# Mainboard.net
KiCad netlist of a schematic drawn in EAGLE
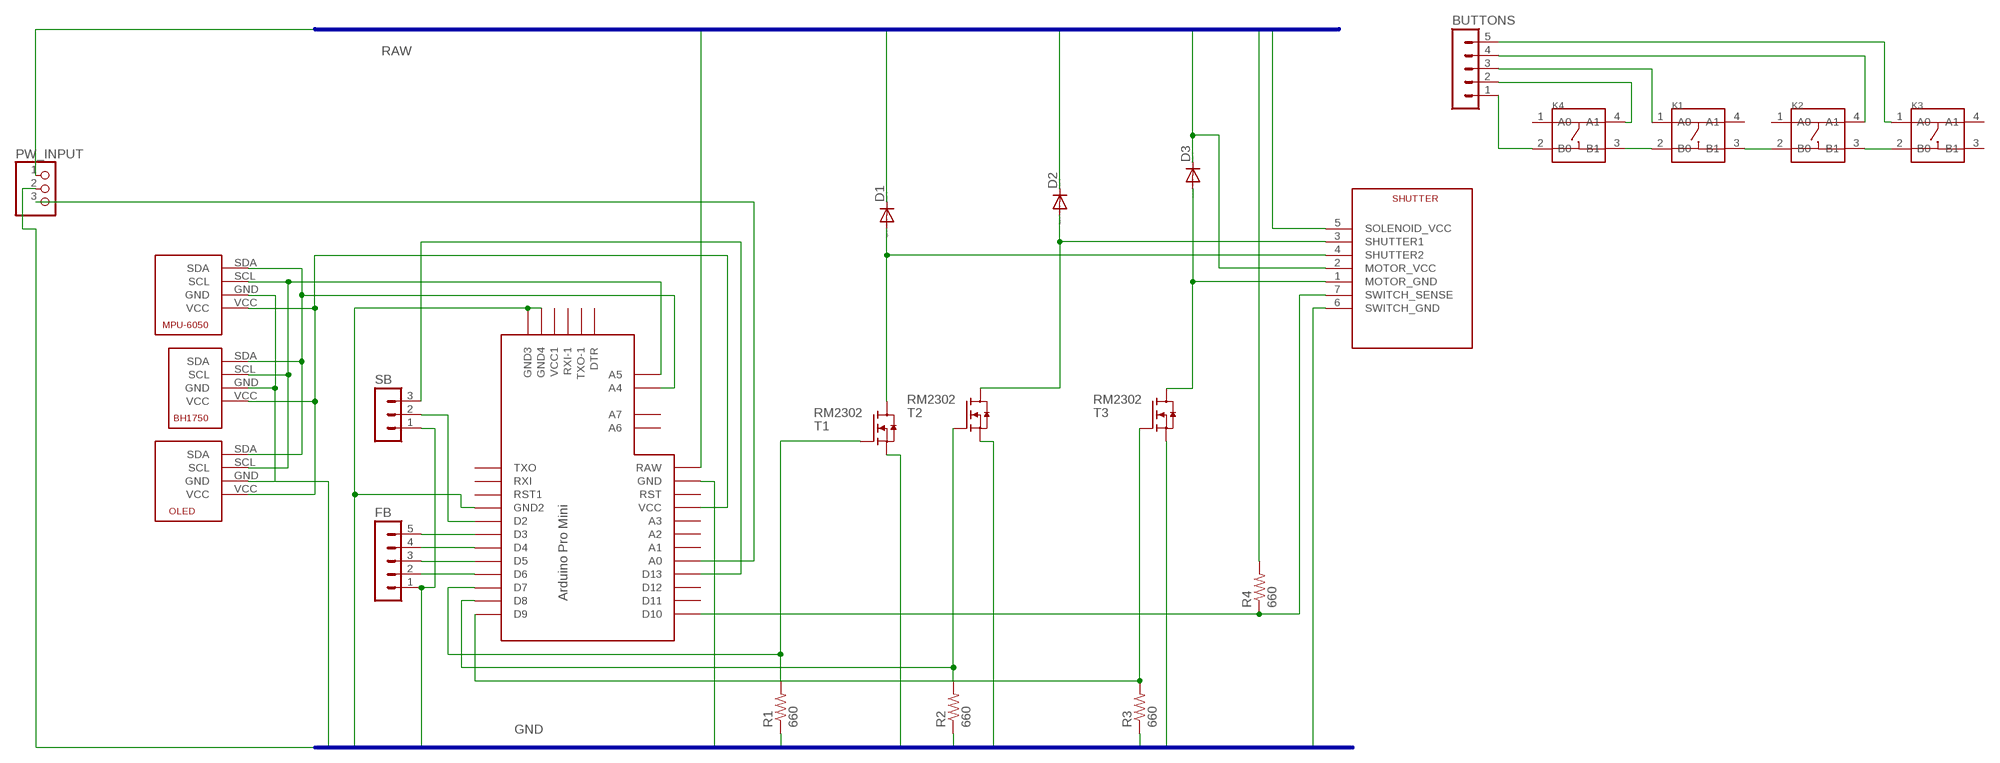
[diagram p0: schematic, sheet 1]

(export (version "E")
  (design (tool "Eeschema 10.0.6"))
  (components
    (comp (ref "BH1750")
      (value "BH1750")
      (footprint "eagle-import:MA04-1")
      (libsource (lib "eagle-import") (part "BH1750"))
    )
    (comp (ref "BUTTONS")
      (value "MA05-1")
      (footprint "eagle-import:MA05-1")
      (libsource (lib "eagle-import") (part "MA05-1"))
    )
    (comp (ref "D1")
      (value "DIODE-D-5")
      (footprint "eagle-import:D-5")
      (libsource (lib "eagle-import") (part "DIODE-D-5"))
    )
    (comp (ref "D2")
      (value "DIODE-D-5")
      (footprint "eagle-import:D-5")
      (libsource (lib "eagle-import") (part "DIODE-D-5"))
    )
    (comp (ref "D3")
      (value "DIODE-D-5")
      (footprint "eagle-import:D-5")
      (libsource (lib "eagle-import") (part "DIODE-D-5"))
    )
    (comp (ref "FB")
      (value "MA05-1")
      (footprint "eagle-import:MA05-1")
      (libsource (lib "eagle-import") (part "MA05-1"))
    )
    (comp (ref "K1")
      (value "SMD-SWITCH-TACTILE-SPST-NO(4P-D6.0MM)")
      (footprint "eagle-import:SW4-SMD-6.0X6.0X5.0MM")
      (fields (field (name "MPN") "DTSM-62K-S-V-T/R(SN431)"))
      (libsource (lib "eagle-import") (part "SMD-SWITCH-TACTILE-SPST-NO(4P-D6.0MM)"))
    )
    (comp (ref "K2")
      (value "SMD-SWITCH-TACTILE-SPST-NO(4P-D6.0MM)")
      (footprint "eagle-import:SW4-SMD-6.0X6.0X5.0MM")
      (fields (field (name "MPN") "DTSM-62K-S-V-T/R(SN431)"))
      (libsource (lib "eagle-import") (part "SMD-SWITCH-TACTILE-SPST-NO(4P-D6.0MM)"))
    )
    (comp (ref "K3")
      (value "SMD-SWITCH-TACTILE-SPST-NO(4P-D6.0MM)")
      (footprint "eagle-import:SW4-SMD-6.0X6.0X5.0MM")
      (fields (field (name "MPN") "DTSM-62K-S-V-T/R(SN431)"))
      (libsource (lib "eagle-import") (part "SMD-SWITCH-TACTILE-SPST-NO(4P-D6.0MM)"))
    )
    (comp (ref "K4")
      (value "SMD-SWITCH-TACTILE-SPST-NO(4P-D6.0MM)")
      (footprint "eagle-import:SW4-SMD-6.0X6.0X5.0MM")
      (fields (field (name "MPN") "DTSM-62K-S-V-T/R(SN431)"))
      (libsource (lib "eagle-import") (part "SMD-SWITCH-TACTILE-SPST-NO(4P-D6.0MM)"))
    )
    (comp (ref "MPU6050")
      (value "MPU-6050")
      (footprint "eagle-import:MA04-1")
      (libsource (lib "eagle-import") (part "MPU-6050"))
    )
    (comp (ref "OLED")
      (value "OLED")
      (footprint "eagle-import:MA04-1")
      (libsource (lib "eagle-import") (part "OLED"))
    )
    (comp (ref "PW_INPUT")
      (value "PINHD-1X3")
      (footprint "eagle-import:1X03")
      (libsource (lib "eagle-import") (part "PINHD-1X3"))
    )
    (comp (ref "R1")
      (value "660")
      (footprint "eagle-import:0204V")
      (libsource (lib "eagle-import") (part "R-US_0204/2V"))
    )
    (comp (ref "R2")
      (value "660")
      (footprint "eagle-import:0204V")
      (libsource (lib "eagle-import") (part "R-US_0204/2V"))
    )
    (comp (ref "R3")
      (value "660")
      (footprint "eagle-import:0204V")
      (libsource (lib "eagle-import") (part "R-US_0204/2V"))
    )
    (comp (ref "R4")
      (value "660")
      (footprint "eagle-import:0204V")
      (libsource (lib "eagle-import") (part "R-US_0204/2V"))
    )
    (comp (ref "SB")
      (value "MA03-1")
      (footprint "eagle-import:MA03-1")
      (libsource (lib "eagle-import") (part "MA03-1"))
    )
    (comp (ref "T1")
      (value "RM2302")
      (footprint "eagle-import:SOT23")
      (libsource (lib "eagle-import") (part "RM2302"))
    )
    (comp (ref "T2")
      (value "RM2302")
      (footprint "eagle-import:SOT23")
      (libsource (lib "eagle-import") (part "RM2302"))
    )
    (comp (ref "T3")
      (value "RM2302")
      (footprint "eagle-import:SOT23")
      (libsource (lib "eagle-import") (part "RM2302"))
    )
    (comp (ref "U$1")
      (value "SHUTTER")
      (footprint "eagle-import:MA07-1")
      (libsource (lib "eagle-import") (part "SHUTTER"))
    )
    (comp (ref "U$7")
      (value "PRO-MINI-2")
      (footprint "eagle-import:PRO-MINI-2")
      (libsource (lib "eagle-import") (part "PRO-MINI-2"))
    )
  )
  (nets
    (net (code "2") (name "/BTG") (class "Default")
      (node (ref "BUTTONS") (pin "1") (pinfunction "1_1") (pintype "passive"))
      (node (ref "K1") (pin "2") (pinfunction "B0_2") (pintype "bidirectional"))
      (node (ref "K1") (pin "3") (pinfunction "B1_3") (pintype "bidirectional"))
      (node (ref "K2") (pin "2") (pinfunction "B0_2") (pintype "bidirectional"))
      (node (ref "K2") (pin "3") (pinfunction "B1_3") (pintype "bidirectional"))
      (node (ref "K3") (pin "2") (pinfunction "B0_2") (pintype "bidirectional"))
      (node (ref "K4") (pin "2") (pinfunction "B0_2") (pintype "bidirectional"))
      (node (ref "K4") (pin "3") (pinfunction "B1_3") (pintype "bidirectional"))
    )
    (net (code "3") (name "/GND") (class "Default")
      (node (ref "BH1750") (pin "GND") (pinfunction "GND_GND") (pintype "power_in"))
      (node (ref "FB") (pin "1") (pinfunction "1_1") (pintype "passive"))
      (node (ref "MPU6050") (pin "GND") (pinfunction "GND_GND") (pintype "power_in"))
      (node (ref "OLED") (pin "GND") (pinfunction "GND_GND") (pintype "power_in"))
      (node (ref "PW_INPUT") (pin "2") (pinfunction "2_2") (pintype "passive"))
      (node (ref "R1") (pin "1") (pinfunction "1_1") (pintype "passive"))
      (node (ref "R2") (pin "1") (pinfunction "1_1") (pintype "passive"))
      (node (ref "R3") (pin "1") (pinfunction "1_1") (pintype "passive"))
      (node (ref "SB") (pin "1") (pinfunction "1_1") (pintype "passive"))
      (node (ref "T1") (pin "SOURCE") (pinfunction "S_SOURCE") (pintype "passive"))
      (node (ref "T2") (pin "SOURCE") (pinfunction "S_SOURCE") (pintype "passive"))
      (node (ref "T3") (pin "SOURCE") (pinfunction "S_SOURCE") (pintype "passive"))
      (node (ref "U$1") (pin "6") (pinfunction "SWITCH_GND_6") (pintype "bidirectional"))
      (node (ref "U$7") (pin "GND") (pinfunction "GND_GND") (pintype "bidirectional"))
      (node (ref "U$7") (pin "GND1") (pinfunction "GND2_GND1") (pintype "bidirectional"))
      (node (ref "U$7") (pin "GND2") (pinfunction "GND3_GND2") (pintype "bidirectional"))
      (node (ref "U$7") (pin "GND3") (pinfunction "GND4_GND3") (pintype "bidirectional"))
    )
    (net (code "4") (name "/VCC") (class "Default")
      (node (ref "D1") (pin "C") (pinfunction "C_C") (pintype "passive"))
      (node (ref "D2") (pin "C") (pinfunction "C_C") (pintype "passive"))
      (node (ref "D3") (pin "C") (pinfunction "C_C") (pintype "passive"))
      (node (ref "PW_INPUT") (pin "1") (pinfunction "1_1") (pintype "passive"))
      (node (ref "R4") (pin "2") (pinfunction "2_2") (pintype "passive"))
      (node (ref "U$1") (pin "2") (pinfunction "MOTOR_VCC_2") (pintype "bidirectional"))
      (node (ref "U$1") (pin "5") (pinfunction "SOLENOID_VCC_5") (pintype "power_in"))
      (node (ref "U$7") (pin "RAW") (pinfunction "RAW_RAW") (pintype "bidirectional"))
    )
    (net (code "7") (name "Net-(BH1750-PadSCL)") (class "Default")
      (node (ref "BH1750") (pin "SCL") (pinfunction "SCL_SCL") (pintype "bidirectional"))
      (node (ref "MPU6050") (pin "SCL") (pinfunction "SCL_SCL") (pintype "bidirectional"))
      (node (ref "OLED") (pin "SCL") (pinfunction "SCL_SCL") (pintype "bidirectional"))
      (node (ref "U$7") (pin "A5") (pinfunction "A5_A5") (pintype "bidirectional"))
    )
    (net (code "8") (name "Net-(BH1750-PadSDA)") (class "Default")
      (node (ref "BH1750") (pin "SDA") (pinfunction "SDA_SDA") (pintype "bidirectional"))
      (node (ref "MPU6050") (pin "SDA") (pinfunction "SDA_SDA") (pintype "bidirectional"))
      (node (ref "OLED") (pin "SDA") (pinfunction "SDA_SDA") (pintype "bidirectional"))
      (node (ref "U$7") (pin "A4") (pinfunction "A4_A4") (pintype "bidirectional"))
    )
    (net (code "9") (name "Net-(BH1750-PadVCC)") (class "Default")
      (node (ref "BH1750") (pin "VCC") (pinfunction "VCC_VCC") (pintype "power_in"))
      (node (ref "MPU6050") (pin "VCC") (pinfunction "VCC_VCC") (pintype "power_in"))
      (node (ref "OLED") (pin "VCC") (pinfunction "VCC_VCC") (pintype "power_in"))
      (node (ref "U$7") (pin "VCC") (pinfunction "VCC_VCC") (pintype "bidirectional"))
    )
    (net (code "10") (name "Net-(FB-Pad2)") (class "Default")
      (node (ref "FB") (pin "2") (pinfunction "2_2") (pintype "passive"))
      (node (ref "U$7") (pin "D6") (pinfunction "D6_D6") (pintype "bidirectional"))
    )
    (net (code "11") (name "Net-(FB-Pad3)") (class "Default")
      (node (ref "FB") (pin "3") (pinfunction "3_3") (pintype "passive"))
      (node (ref "U$7") (pin "D5") (pinfunction "D5_D5") (pintype "bidirectional"))
    )
    (net (code "12") (name "Net-(FB-Pad4)") (class "Default")
      (node (ref "FB") (pin "4") (pinfunction "4_4") (pintype "passive"))
      (node (ref "U$7") (pin "D4") (pinfunction "D4_D4") (pintype "bidirectional"))
    )
    (net (code "13") (name "Net-(FB-Pad5)") (class "Default")
      (node (ref "FB") (pin "5") (pinfunction "5_5") (pintype "passive"))
      (node (ref "U$7") (pin "D3") (pinfunction "D3_D3") (pintype "bidirectional"))
    )
    (net (code "14") (name "Net-(K1-A0)") (class "Default")
      (node (ref "BUTTONS") (pin "3") (pinfunction "3_3") (pintype "passive"))
      (node (ref "K1") (pin "1") (pinfunction "A0_1") (pintype "bidirectional"))
    )
    (net (code "15") (name "Net-(K2-A1)") (class "Default")
      (node (ref "BUTTONS") (pin "4") (pinfunction "4_4") (pintype "passive"))
      (node (ref "K2") (pin "4") (pinfunction "A1_4") (pintype "bidirectional"))
    )
    (net (code "16") (name "Net-(K3-A0)") (class "Default")
      (node (ref "BUTTONS") (pin "5") (pinfunction "5_5") (pintype "passive"))
      (node (ref "K3") (pin "1") (pinfunction "A0_1") (pintype "bidirectional"))
    )
    (net (code "17") (name "Net-(K4-A1)") (class "Default")
      (node (ref "BUTTONS") (pin "2") (pinfunction "2_2") (pintype "passive"))
      (node (ref "K4") (pin "4") (pinfunction "A1_4") (pintype "bidirectional"))
    )
    (net (code "18") (name "Net-(PW_INPUT-Pad3)") (class "Default")
      (node (ref "PW_INPUT") (pin "3") (pinfunction "3_3") (pintype "passive"))
      (node (ref "U$7") (pin "A0") (pinfunction "A0_A0") (pintype "bidirectional"))
    )
    (net (code "19") (name "Net-(SB-Pad2)") (class "Default")
      (node (ref "SB") (pin "2") (pinfunction "2_2") (pintype "passive"))
      (node (ref "U$7") (pin "D2") (pinfunction "D2_D2") (pintype "bidirectional"))
    )
    (net (code "20") (name "Net-(SB-Pad3)") (class "Default")
      (node (ref "SB") (pin "3") (pinfunction "3_3") (pintype "passive"))
      (node (ref "U$7") (pin "D13") (pinfunction "D13_D13") (pintype "bidirectional"))
    )
    (net (code "21") (name "Net-(T1-D)") (class "Default")
      (node (ref "D1") (pin "A") (pinfunction "A_A") (pintype "passive"))
      (node (ref "T1") (pin "DRAIN") (pinfunction "D_DRAIN") (pintype "passive"))
      (node (ref "U$1") (pin "4") (pinfunction "SHUTTER2_4") (pintype "bidirectional"))
    )
    (net (code "22") (name "Net-(T1-G)") (class "Default")
      (node (ref "R1") (pin "2") (pinfunction "2_2") (pintype "passive"))
      (node (ref "T1") (pin "GATE") (pinfunction "G_GATE") (pintype "passive"))
      (node (ref "U$7") (pin "D7") (pinfunction "D7_D7") (pintype "bidirectional"))
    )
    (net (code "23") (name "Net-(T2-D)") (class "Default")
      (node (ref "D2") (pin "A") (pinfunction "A_A") (pintype "passive"))
      (node (ref "T2") (pin "DRAIN") (pinfunction "D_DRAIN") (pintype "passive"))
      (node (ref "U$1") (pin "3") (pinfunction "SHUTTER1_3") (pintype "bidirectional"))
    )
    (net (code "24") (name "Net-(T2-G)") (class "Default")
      (node (ref "R2") (pin "2") (pinfunction "2_2") (pintype "passive"))
      (node (ref "T2") (pin "GATE") (pinfunction "G_GATE") (pintype "passive"))
      (node (ref "U$7") (pin "D8") (pinfunction "D8_D8") (pintype "bidirectional"))
    )
    (net (code "25") (name "Net-(T3-D)") (class "Default")
      (node (ref "D3") (pin "A") (pinfunction "A_A") (pintype "passive"))
      (node (ref "T3") (pin "DRAIN") (pinfunction "D_DRAIN") (pintype "passive"))
      (node (ref "U$1") (pin "1") (pinfunction "MOTOR_GND_1") (pintype "bidirectional"))
    )
    (net (code "26") (name "Net-(T3-G)") (class "Default")
      (node (ref "R3") (pin "2") (pinfunction "2_2") (pintype "passive"))
      (node (ref "T3") (pin "GATE") (pinfunction "G_GATE") (pintype "passive"))
      (node (ref "U$7") (pin "D9") (pinfunction "D9_D9") (pintype "bidirectional"))
    )
    (net (code "27") (name "Net-(U$1-SWITCH_SENSE)") (class "Default")
      (node (ref "R4") (pin "1") (pinfunction "1_1") (pintype "passive"))
      (node (ref "U$1") (pin "7") (pinfunction "SWITCH_SENSE_7") (pintype "bidirectional"))
      (node (ref "U$7") (pin "D10") (pinfunction "D10_D10") (pintype "bidirectional"))
    )
    (net (code "28") (name "unconnected-(K1-A1-Pad4)") (class "Default")
      (node (ref "K1") (pin "4") (pinfunction "A1_4") (pintype "bidirectional"))
    )
    (net (code "29") (name "unconnected-(K2-A0-Pad1)") (class "Default")
      (node (ref "K2") (pin "1") (pinfunction "A0_1") (pintype "bidirectional"))
    )
    (net (code "30") (name "unconnected-(K3-A1-Pad4)") (class "Default")
      (node (ref "K3") (pin "4") (pinfunction "A1_4") (pintype "bidirectional"))
    )
    (net (code "31") (name "unconnected-(K3-B1-Pad3)") (class "Default")
      (node (ref "K3") (pin "3") (pinfunction "B1_3") (pintype "bidirectional"))
    )
    (net (code "32") (name "unconnected-(K4-A0-Pad1)") (class "Default")
      (node (ref "K4") (pin "1") (pinfunction "A0_1") (pintype "bidirectional"))
    )
    (net (code "33") (name "unconnected-(U$7-PadA1)") (class "Default")
      (node (ref "U$7") (pin "A1") (pinfunction "A1_A1") (pintype "bidirectional"))
    )
    (net (code "34") (name "unconnected-(U$7-PadA2)") (class "Default")
      (node (ref "U$7") (pin "A2") (pinfunction "A2_A2") (pintype "bidirectional"))
    )
    (net (code "35") (name "unconnected-(U$7-PadA3)") (class "Default")
      (node (ref "U$7") (pin "A3") (pinfunction "A3_A3") (pintype "bidirectional"))
    )
    (net (code "36") (name "unconnected-(U$7-PadA6)") (class "Default")
      (node (ref "U$7") (pin "A6") (pinfunction "A6_A6") (pintype "bidirectional"))
    )
    (net (code "37") (name "unconnected-(U$7-PadA7)") (class "Default")
      (node (ref "U$7") (pin "A7") (pinfunction "A7_A7") (pintype "bidirectional"))
    )
    (net (code "38") (name "unconnected-(U$7-PadD11)") (class "Default")
      (node (ref "U$7") (pin "D11") (pinfunction "D11_D11") (pintype "bidirectional"))
    )
    (net (code "39") (name "unconnected-(U$7-PadD12)") (class "Default")
      (node (ref "U$7") (pin "D12") (pinfunction "D12_D12") (pintype "bidirectional"))
    )
    (net (code "40") (name "unconnected-(U$7-PadDTR)") (class "Default")
      (node (ref "U$7") (pin "DTR") (pinfunction "DTR_DTR") (pintype "bidirectional"))
    )
    (net (code "41") (name "unconnected-(U$7-PadRST)") (class "Default")
      (node (ref "U$7") (pin "RST") (pinfunction "RST_RST") (pintype "bidirectional"))
    )
    (net (code "42") (name "unconnected-(U$7-PadRST1)") (class "Default")
      (node (ref "U$7") (pin "RST1") (pinfunction "RST1_RST1") (pintype "bidirectional"))
    )
    (net (code "43") (name "unconnected-(U$7-PadRXI)") (class "Default")
      (node (ref "U$7") (pin "RXI") (pinfunction "RXI_RXI") (pintype "bidirectional"))
    )
    (net (code "44") (name "unconnected-(U$7-PadRXI-1)") (class "Default")
      (node (ref "U$7") (pin "RXI-1") (pinfunction "RXI-1_RXI-1") (pintype "bidirectional"))
    )
    (net (code "45") (name "unconnected-(U$7-PadTXO)") (class "Default")
      (node (ref "U$7") (pin "TXO") (pinfunction "TXO_TXO") (pintype "bidirectional"))
    )
    (net (code "46") (name "unconnected-(U$7-PadTXO-1)") (class "Default")
      (node (ref "U$7") (pin "TXO-1") (pinfunction "TXO-1_TXO-1") (pintype "bidirectional"))
    )
    (net (code "47") (name "unconnected-(U$7-PadVCC1)") (class "Default")
      (node (ref "U$7") (pin "VCC1") (pinfunction "VCC1_VCC1") (pintype "bidirectional"))
    )
  )
)
